# ETH_JTAG_SD.net
KiCad netlist of a schematic drawn in Altium Designer
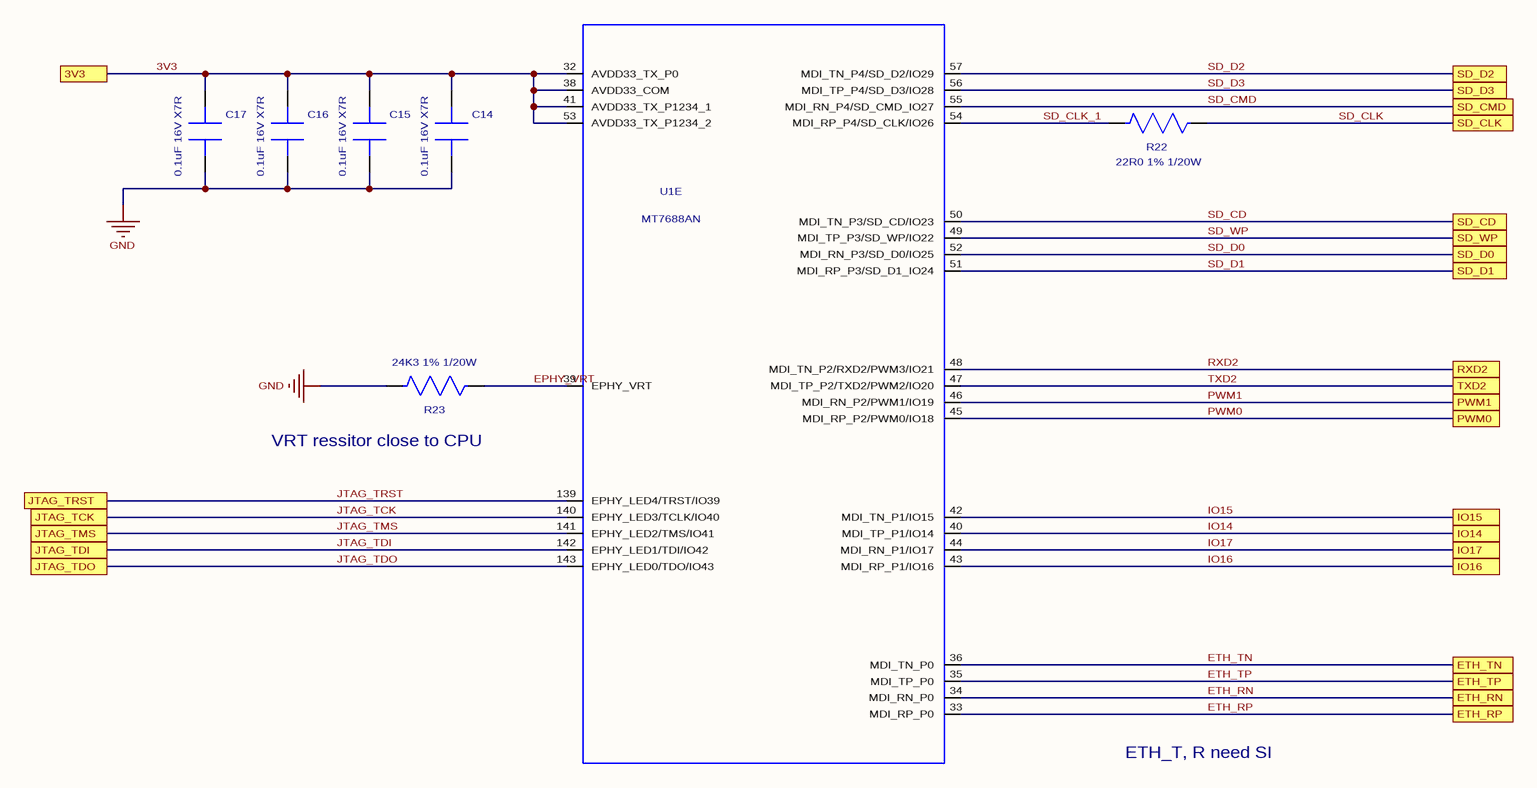
[diagram p0: ETH_JTAG_SD.SchDoc]

(export (version "E")
  (design (tool "Eeschema 10.0.6"))
  (components
    (comp (ref "C14")
      (value "0.1uF 16V X7R")
      (footprint "C0201")
      (description "CAP CER 0.1UF 16V X7R 0201")
      (fields
        (field (name "PART NUMBER") "GRM033Z71C104KE14D")
        (field (name "MANUFACTURER") "Murata Electronics")
      )
      (libsource (lib "NetworkModule") (part "CAP0201-104-16V-X7R"))
    )
    (comp (ref "C15")
      (value "0.1uF 16V X7R")
      (footprint "C0201")
      (description "CAP CER 0.1UF 16V X7R 0201")
      (fields
        (field (name "PART NUMBER") "GRM033Z71C104KE14D")
        (field (name "MANUFACTURER") "Murata Electronics")
      )
      (libsource (lib "NetworkModule") (part "CAP0201-104-16V-X7R"))
    )
    (comp (ref "C16")
      (value "0.1uF 16V X7R")
      (footprint "C0201")
      (description "CAP CER 0.1UF 16V X7R 0201")
      (fields
        (field (name "PART NUMBER") "GRM033Z71C104KE14D")
        (field (name "MANUFACTURER") "Murata Electronics")
      )
      (libsource (lib "NetworkModule") (part "CAP0201-104-16V-X7R"))
    )
    (comp (ref "C17")
      (value "0.1uF 16V X7R")
      (footprint "C0201")
      (description "CAP CER 0.1UF 16V X7R 0201")
      (fields
        (field (name "PART NUMBER") "GRM033Z71C104KE14D")
        (field (name "MANUFACTURER") "Murata Electronics")
      )
      (libsource (lib "NetworkModule") (part "CAP0201-104-16V-X7R"))
    )
    (comp (ref "R22")
      (value "22R0 1% 1/20W")
      (footprint "R0201")
      (description "RES 22 OHM 1% 1/20W 0201")
      (fields (field (name "MANUFACTURER") "Yageo") (field (name "PART NUMBER") "RC0201FR-0722RL"))
      (libsource (lib "NetworkModule") (part "RES0201-22R0"))
    )
    (comp (ref "R23")
      (value "24K3 1% 1/20W")
      (footprint "R0201")
      (description "RES 24.3K OHM 1% 1/20W 0201")
      (fields (field (name "PART NUMBER") "RC0201FR-0724K3L") (field (name "MANUFACTURER") "YAGEO"))
      (libsource (lib "NetworkModule") (part "RES0201-24K3"))
    )
    (comp (ref "U1")
      (value "MT7688AN")
      (footprint "DR-QFN-128")
      (description "580Mhz 32bits Networking Processor")
      (fields (field (name "MANUFACTURER") "MediaTek Inc"))
      (libsource (lib "*") (part "MT7688AN"))
    )
  )
  (nets
    (net (code "1") (name "/3V3") (class "Default")
      (node (ref "C14") (pin "1") (pinfunction "1_1") (pintype "passive"))
      (node (ref "C15") (pin "1") (pinfunction "1_1") (pintype "passive"))
      (node (ref "C16") (pin "1") (pinfunction "1_1") (pintype "passive"))
      (node (ref "C17") (pin "1") (pinfunction "1_1") (pintype "passive"))
      (node (ref "U1") (pin "32") (pinfunction "AVDD33_TX_P0_32") (pintype "passive"))
      (node (ref "U1") (pin "38") (pinfunction "AVDD33_COM_38") (pintype "passive"))
      (node (ref "U1") (pin "41") (pinfunction "AVDD33_TX_P1234_1_41") (pintype "passive"))
      (node (ref "U1") (pin "53") (pinfunction "AVDD33_TX_P1234_2_53") (pintype "passive"))
    )
    (net (code "2") (name "/EPHY_VRT") (class "Default")
      (node (ref "R23") (pin "1") (pinfunction "1_1") (pintype "passive"))
      (node (ref "U1") (pin "39") (pinfunction "EPHY_VRT_39") (pintype "passive"))
    )
    (net (code "3") (name "/ETH_RN") (class "Default")
      (node (ref "U1") (pin "34") (pinfunction "MDI_RN_P0_34") (pintype "passive"))
    )
    (net (code "4") (name "/ETH_RP") (class "Default")
      (node (ref "U1") (pin "33") (pinfunction "MDI_RP_P0_33") (pintype "passive"))
    )
    (net (code "5") (name "/ETH_TN") (class "Default")
      (node (ref "U1") (pin "36") (pinfunction "MDI_TN_P0_36") (pintype "passive"))
    )
    (net (code "6") (name "/ETH_TP") (class "Default")
      (node (ref "U1") (pin "35") (pinfunction "MDI_TP_P0_35") (pintype "passive"))
    )
    (net (code "7") (name "/IO14") (class "Default")
      (node (ref "U1") (pin "40") (pinfunction "MDI_TP_P1/IO14_40") (pintype "passive"))
    )
    (net (code "8") (name "/IO15") (class "Default")
      (node (ref "U1") (pin "42") (pinfunction "MDI_TN_P1/IO15_42") (pintype "passive"))
    )
    (net (code "9") (name "/IO16") (class "Default")
      (node (ref "U1") (pin "43") (pinfunction "MDI_RP_P1/IO16_43") (pintype "passive"))
    )
    (net (code "10") (name "/IO17") (class "Default")
      (node (ref "U1") (pin "44") (pinfunction "MDI_RN_P1/IO17_44") (pintype "passive"))
    )
    (net (code "11") (name "/JTAG_TCK") (class "Default")
      (node (ref "U1") (pin "140") (pinfunction "EPHY_LED3/TCLK/IO40_140") (pintype "passive"))
    )
    (net (code "12") (name "/JTAG_TDI") (class "Default")
      (node (ref "U1") (pin "142") (pinfunction "EPHY_LED1/TDI/IO42_142") (pintype "passive"))
    )
    (net (code "13") (name "/JTAG_TDO") (class "Default")
      (node (ref "U1") (pin "143") (pinfunction "EPHY_LED0/TDO/IO43_143") (pintype "passive"))
    )
    (net (code "14") (name "/JTAG_TMS") (class "Default")
      (node (ref "U1") (pin "141") (pinfunction "EPHY_LED2/TMS/IO41_141") (pintype "passive"))
    )
    (net (code "15") (name "/JTAG_TRST") (class "Default")
      (node (ref "U1") (pin "139") (pinfunction "EPHY_LED4/TRST/IO39_139") (pintype "passive"))
    )
    (net (code "16") (name "/PWM0") (class "Default")
      (node (ref "U1") (pin "45") (pinfunction "MDI_RP_P2/PWM0/IO18_45") (pintype "passive"))
    )
    (net (code "17") (name "/PWM1") (class "Default")
      (node (ref "U1") (pin "46") (pinfunction "MDI_RN_P2/PWM1/IO19_46") (pintype "passive"))
    )
    (net (code "18") (name "/RXD2") (class "Default")
      (node (ref "U1") (pin "48") (pinfunction "MDI_TN_P2/RXD2/PWM3/IO21_48") (pintype "passive"))
    )
    (net (code "19") (name "/SD_CD") (class "Default")
      (node (ref "U1") (pin "50") (pinfunction "MDI_TN_P3/SD_CD/IO23_50") (pintype "passive"))
    )
    (net (code "20") (name "/SD_CLK") (class "Default")
      (node (ref "R22") (pin "1") (pinfunction "1_1") (pintype "passive"))
    )
    (net (code "21") (name "/SD_CLK_1") (class "Default")
      (node (ref "R22") (pin "2") (pinfunction "2_2") (pintype "passive"))
      (node (ref "U1") (pin "54") (pinfunction "MDI_RP_P4/SD_CLK/IO26_54") (pintype "passive"))
    )
    (net (code "22") (name "/SD_CMD") (class "Default")
      (node (ref "U1") (pin "55") (pinfunction "MDI_RN_P4/SD_CMD_IO27_55") (pintype "passive"))
    )
    (net (code "23") (name "/SD_D0") (class "Default")
      (node (ref "U1") (pin "52") (pinfunction "MDI_RN_P3/SD_D0/IO25_52") (pintype "passive"))
    )
    (net (code "24") (name "/SD_D1") (class "Default")
      (node (ref "U1") (pin "51") (pinfunction "MDI_RP_P3/SD_D1_IO24_51") (pintype "passive"))
    )
    (net (code "25") (name "/SD_D2") (class "Default")
      (node (ref "U1") (pin "57") (pinfunction "MDI_TN_P4/SD_D2/IO29_57") (pintype "passive"))
    )
    (net (code "26") (name "/SD_D3") (class "Default")
      (node (ref "U1") (pin "56") (pinfunction "MDI_TP_P4/SD_D3/IO28_56") (pintype "passive"))
    )
    (net (code "27") (name "/SD_WP") (class "Default")
      (node (ref "U1") (pin "49") (pinfunction "MDI_TP_P3/SD_WP/IO22_49") (pintype "passive"))
    )
    (net (code "28") (name "/TXD2") (class "Default")
      (node (ref "U1") (pin "47") (pinfunction "MDI_TP_P2/TXD2/PWM2/IO20_47") (pintype "passive"))
    )
    (net (code "29") (name "GND") (class "Default")
      (node (ref "C14") (pin "2") (pinfunction "2_2") (pintype "passive"))
      (node (ref "C15") (pin "2") (pinfunction "2_2") (pintype "passive"))
      (node (ref "C16") (pin "2") (pinfunction "2_2") (pintype "passive"))
      (node (ref "C17") (pin "2") (pinfunction "2_2") (pintype "passive"))
      (node (ref "R23") (pin "2") (pinfunction "2_2") (pintype "passive"))
    )
  )
)
